# Schema.net
KiCad netlist of a schematic drawn in EAGLE
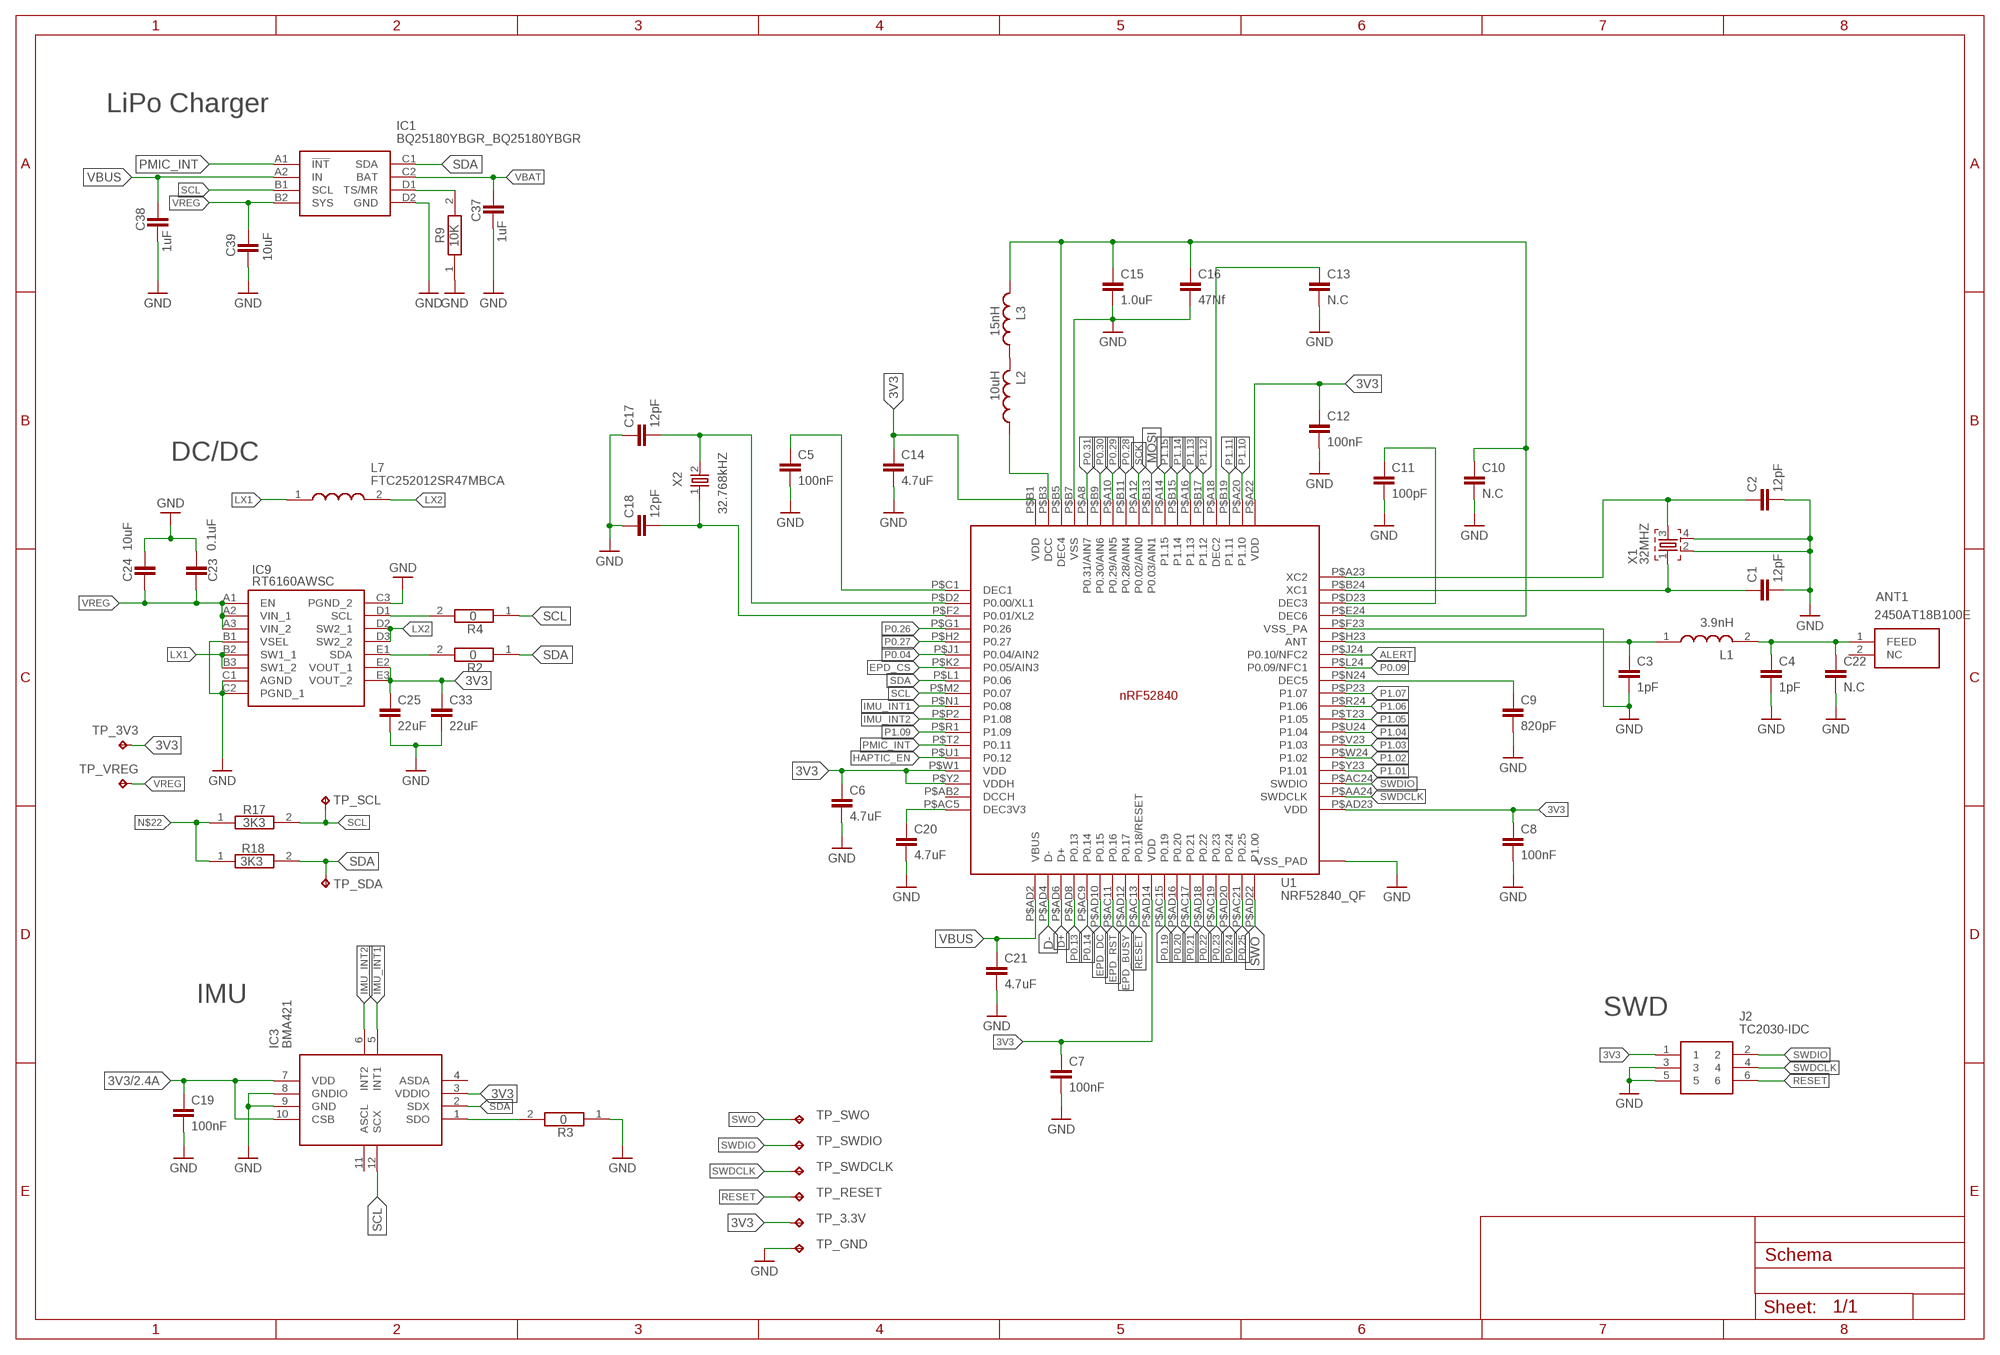
[diagram p0: schematic, sheet 1, part 1 of 2]
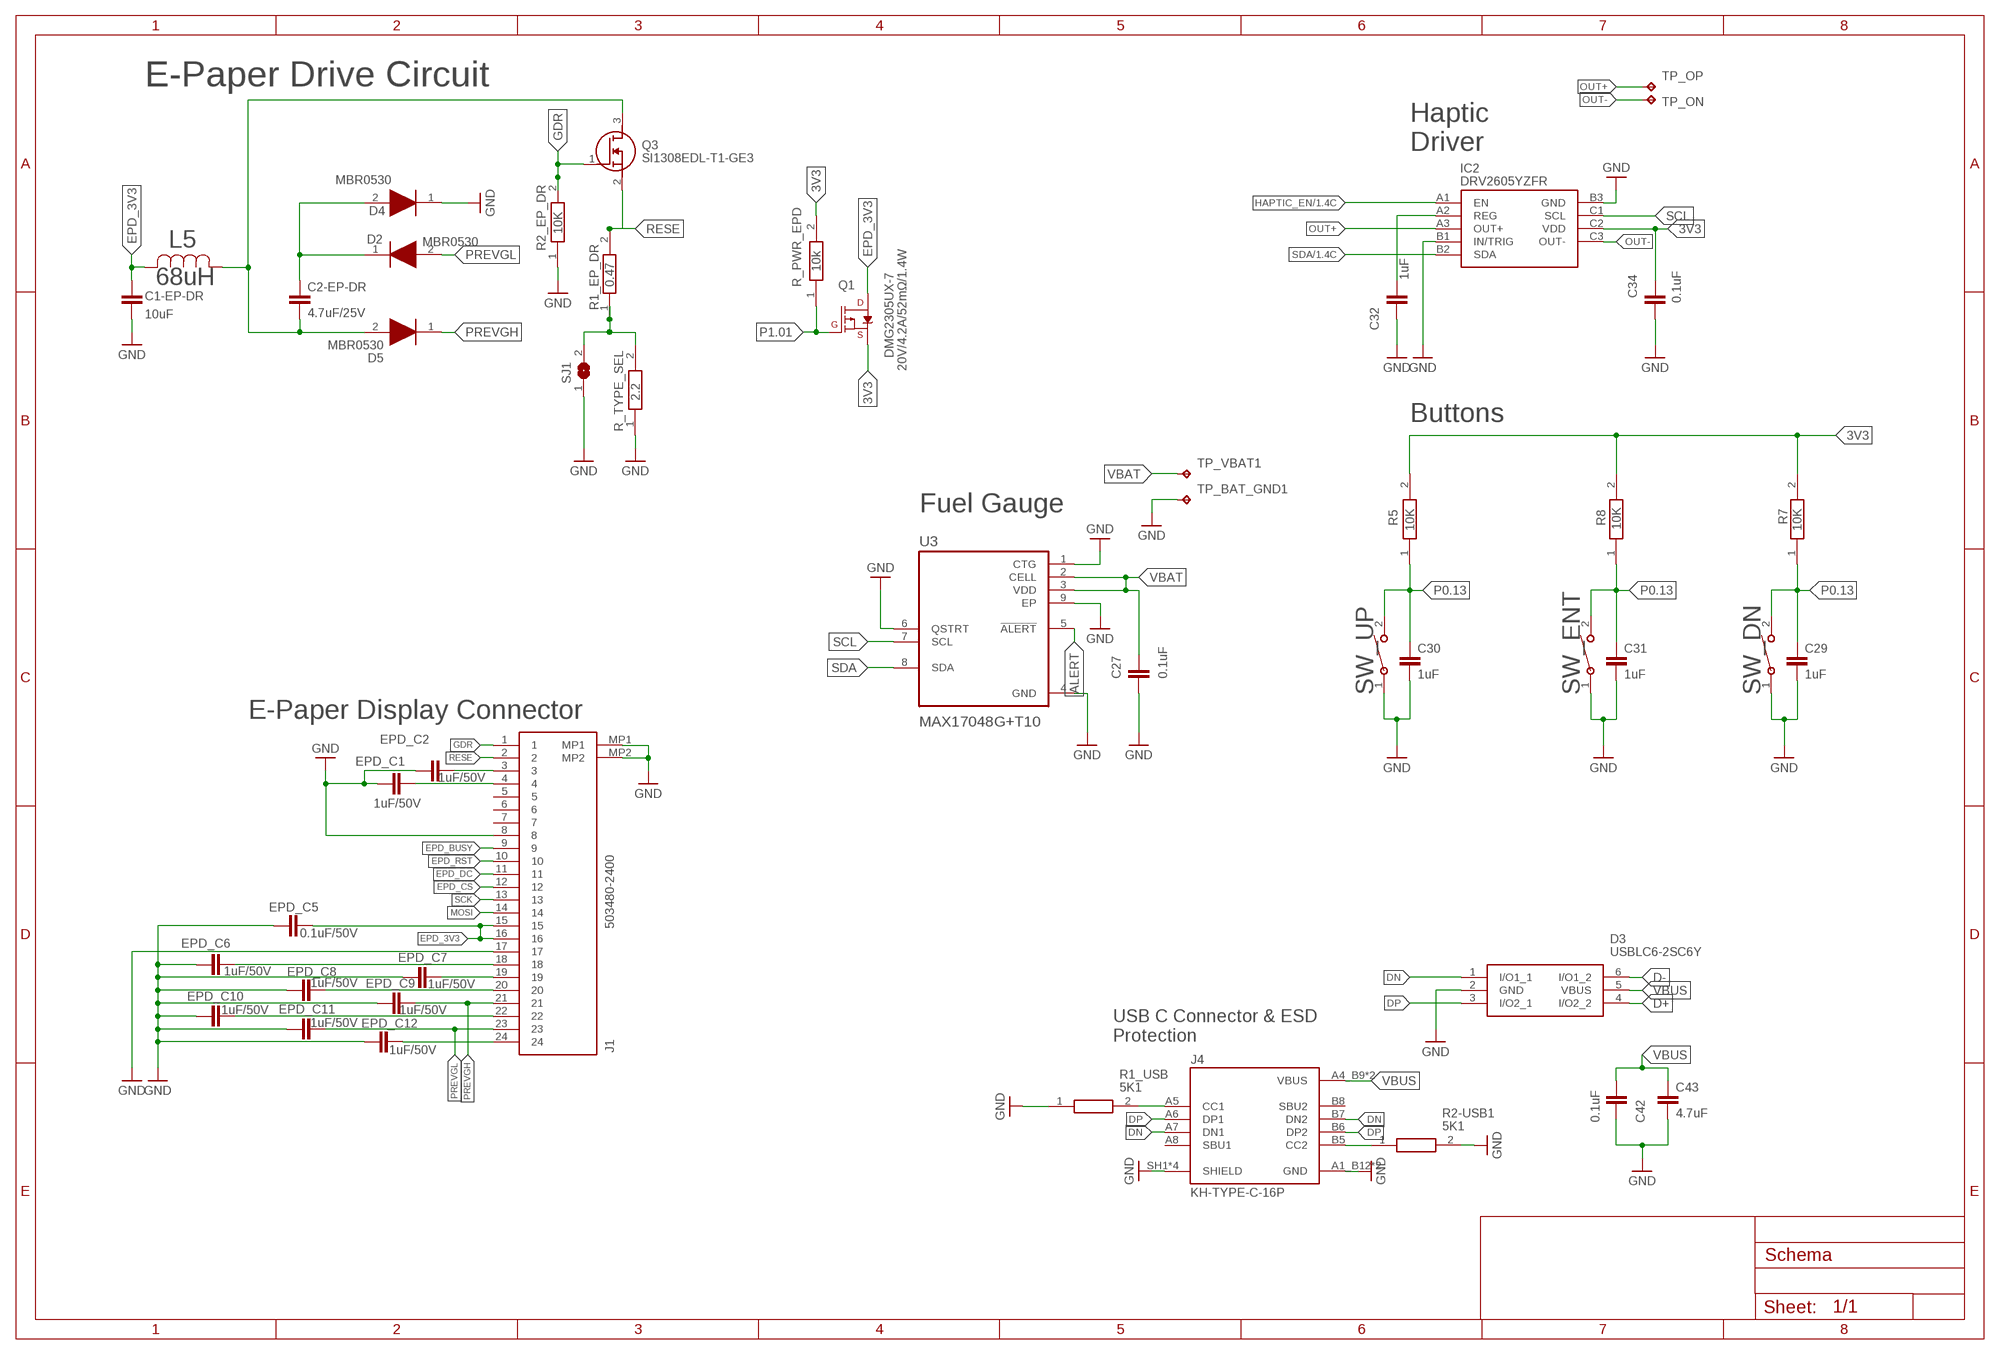
[diagram p1: schematic, sheet 1, part 2 of 2]

(export (version "E")
  (design (tool "Eeschema 10.0.6"))
  (components
    (comp (ref "ANT1")
      (value "2450AT18B100E")
      (footprint "eagle-import:2450AT18B100E_ANTC3216X140N")
      (fields (field (name "MOUSER_PART_NUMBER") "609-2450AT18B100E"))
      (libsource (lib "eagle-import") (part "2450AT18B100E_2450AT18B100E"))
    )
    (comp (ref "C1")
      (value "12pF")
      (footprint "eagle-import:NORDIC_NRF_3_RESC0201_L")
      (libsource (lib "eagle-import") (part "NORDIC_NRF_3_CAPACITOR_0201_L"))
    )
    (comp (ref "C1-EP-DR")
      (value "10uF")
      (footprint "eagle-import:NORDIC_NRF_3_RESC0402_L")
      (libsource (lib "eagle-import") (part "NORDIC_NRF_3_CAPACITOR_0402_L"))
    )
    (comp (ref "C2")
      (value "12pF")
      (footprint "eagle-import:NORDIC_NRF_3_RESC0201_L")
      (libsource (lib "eagle-import") (part "NORDIC_NRF_3_CAPACITOR_0201_L"))
    )
    (comp (ref "C2-EP-DR")
      (value "4.7uF/25V")
      (footprint "eagle-import:NORDIC_NRF_3_RESC0402_L")
      (libsource (lib "eagle-import") (part "NORDIC_NRF_3_CAPACITOR_0402_L"))
    )
    (comp (ref "C3")
      (value "1pF")
      (footprint "eagle-import:NORDIC_NRF_3_RESC0201_L")
      (libsource (lib "eagle-import") (part "NORDIC_NRF_3_CAPACITOR_0201_L"))
    )
    (comp (ref "C4")
      (value "1pF")
      (footprint "eagle-import:NORDIC_NRF_3_RESC0201_L")
      (libsource (lib "eagle-import") (part "NORDIC_NRF_3_CAPACITOR_0201_L"))
    )
    (comp (ref "C5")
      (value "100nF")
      (footprint "eagle-import:NORDIC_NRF_3_RESC0201_L")
      (libsource (lib "eagle-import") (part "NORDIC_NRF_3_CAPACITOR_0201_L"))
    )
    (comp (ref "C6")
      (value "4.7uF")
      (footprint "eagle-import:NORDIC_NRF_3_RESC0402_L")
      (libsource (lib "eagle-import") (part "NORDIC_NRF_3_CAPACITOR_0402_L"))
    )
    (comp (ref "C7")
      (value "100nF")
      (footprint "eagle-import:NORDIC_NRF_3_RESC0201_L")
      (libsource (lib "eagle-import") (part "NORDIC_NRF_3_CAPACITOR_0201_L"))
    )
    (comp (ref "C8")
      (value "100nF")
      (footprint "eagle-import:NORDIC_NRF_3_RESC0201_L")
      (libsource (lib "eagle-import") (part "NORDIC_NRF_3_CAPACITOR_0201_L"))
    )
    (comp (ref "C9")
      (value "820pF")
      (footprint "eagle-import:NORDIC_NRF_3_RESC0201_L")
      (libsource (lib "eagle-import") (part "NORDIC_NRF_3_CAPACITOR_0201_L"))
    )
    (comp (ref "C10")
      (value "N.C")
      (footprint "eagle-import:NORDIC_NRF_3_RESC0201_L")
      (libsource (lib "eagle-import") (part "NORDIC_NRF_3_CAPACITOR_0201_L"))
    )
    (comp (ref "C11")
      (value "100pF")
      (footprint "eagle-import:NORDIC_NRF_3_RESC0201_L")
      (libsource (lib "eagle-import") (part "NORDIC_NRF_3_CAPACITOR_0201_L"))
    )
    (comp (ref "C12")
      (value "100nF")
      (footprint "eagle-import:NORDIC_NRF_3_RESC0201_L")
      (libsource (lib "eagle-import") (part "NORDIC_NRF_3_CAPACITOR_0201_L"))
    )
    (comp (ref "C13")
      (value "N.C")
      (footprint "eagle-import:NORDIC_NRF_3_RESC0201_L")
      (libsource (lib "eagle-import") (part "NORDIC_NRF_3_CAPACITOR_0201_L"))
    )
    (comp (ref "C14")
      (value "4.7uF")
      (footprint "eagle-import:NORDIC_NRF_3_RESC0402_L")
      (libsource (lib "eagle-import") (part "NORDIC_NRF_3_CAPACITOR_0402_L"))
    )
    (comp (ref "C15")
      (value "1.0uF")
      (footprint "eagle-import:NORDIC_NRF_3_RESC0402_L")
      (libsource (lib "eagle-import") (part "NORDIC_NRF_3_CAPACITOR_0402_L"))
    )
    (comp (ref "C16")
      (value "47Nf")
      (footprint "eagle-import:NORDIC_NRF_3_RESC0201_L")
      (libsource (lib "eagle-import") (part "NORDIC_NRF_3_CAPACITOR_0201_L"))
    )
    (comp (ref "C17")
      (value "12pF")
      (footprint "eagle-import:NORDIC_NRF_3_RESC0201_L")
      (libsource (lib "eagle-import") (part "NORDIC_NRF_3_CAPACITOR_0201_L"))
    )
    (comp (ref "C18")
      (value "12pF")
      (footprint "eagle-import:NORDIC_NRF_3_RESC0201_L")
      (libsource (lib "eagle-import") (part "NORDIC_NRF_3_CAPACITOR_0201_L"))
    )
    (comp (ref "C19")
      (value "100nF")
      (footprint "eagle-import:NORDIC_NRF_3_RESC0201_L")
      (libsource (lib "eagle-import") (part "NORDIC_NRF_3_CAPACITOR_0201_L"))
    )
    (comp (ref "C20")
      (value "4.7uF")
      (footprint "eagle-import:NORDIC_NRF_3_RESC0402_L")
      (libsource (lib "eagle-import") (part "NORDIC_NRF_3_CAPACITOR_0402_L"))
    )
    (comp (ref "C21")
      (value "4.7uF")
      (footprint "eagle-import:NORDIC_NRF_3_RESC0402_L")
      (libsource (lib "eagle-import") (part "NORDIC_NRF_3_CAPACITOR_0402_L"))
    )
    (comp (ref "C22")
      (value "N.C")
      (footprint "eagle-import:NORDIC_NRF_3_RESC0201_L")
      (libsource (lib "eagle-import") (part "NORDIC_NRF_3_CAPACITOR_0201_L"))
    )
    (comp (ref "C23")
      (value "0.1uF")
      (footprint "eagle-import:NORDIC_NRF_3_RESC0402_L")
      (libsource (lib "eagle-import") (part "NORDIC_NRF_3_CAPACITOR_0402_L"))
    )
    (comp (ref "C24")
      (value "10uF")
      (footprint "eagle-import:NORDIC_NRF_3_RESC0201_L")
      (libsource (lib "eagle-import") (part "NORDIC_NRF_3_CAPACITOR_0201_L"))
    )
    (comp (ref "C25")
      (value "22uF")
      (footprint "eagle-import:NORDIC_NRF_3_RESC0402_L")
      (libsource (lib "eagle-import") (part "NORDIC_NRF_3_CAPACITOR_0402_L"))
    )
    (comp (ref "C27")
      (value "0.1uF")
      (footprint "eagle-import:NORDIC_NRF_3_RESC0201_L")
      (libsource (lib "eagle-import") (part "NORDIC_NRF_3_CAPACITOR_0201_L"))
    )
    (comp (ref "C29")
      (value "1uF")
      (footprint "eagle-import:NORDIC_NRF_3_RESC0402_L")
      (libsource (lib "eagle-import") (part "NORDIC_NRF_3_CAPACITOR_0402_L"))
    )
    (comp (ref "C30")
      (value "1uF")
      (footprint "eagle-import:NORDIC_NRF_3_RESC0402_L")
      (libsource (lib "eagle-import") (part "NORDIC_NRF_3_CAPACITOR_0402_L"))
    )
    (comp (ref "C31")
      (value "1uF")
      (footprint "eagle-import:NORDIC_NRF_3_RESC0402_L")
      (libsource (lib "eagle-import") (part "NORDIC_NRF_3_CAPACITOR_0402_L"))
    )
    (comp (ref "C32")
      (value "1uF")
      (footprint "eagle-import:NORDIC_NRF_3_RESC0402_L")
      (libsource (lib "eagle-import") (part "NORDIC_NRF_3_CAPACITOR_0402_L"))
    )
    (comp (ref "C33")
      (value "22uF")
      (footprint "eagle-import:NORDIC_NRF_3_RESC0402_L")
      (libsource (lib "eagle-import") (part "NORDIC_NRF_3_CAPACITOR_0402_L"))
    )
    (comp (ref "C34")
      (value "0.1uF")
      (footprint "eagle-import:NORDIC_NRF_3_RESC0201_L")
      (libsource (lib "eagle-import") (part "NORDIC_NRF_3_CAPACITOR_0201_L"))
    )
    (comp (ref "C37")
      (value "1uF")
      (footprint "eagle-import:PERFECT_0402_0402")
      (libsource (lib "eagle-import") (part "PERFECT_0402_CAP_0402"))
    )
    (comp (ref "C38")
      (value "1uF")
      (footprint "eagle-import:PERFECT_0402_0402")
      (libsource (lib "eagle-import") (part "PERFECT_0402_CAP_0402"))
    )
    (comp (ref "C39")
      (value "10uF")
      (footprint "eagle-import:PERFECT_0402_0402")
      (libsource (lib "eagle-import") (part "PERFECT_0402_CAP_0402"))
    )
    (comp (ref "C42")
      (value "0.1uF")
      (footprint "eagle-import:NORDIC_NRF_3_RESC0201_L")
      (libsource (lib "eagle-import") (part "NORDIC_NRF_3_CAPACITOR_0201_L"))
    )
    (comp (ref "C43")
      (value "4.7uF")
      (footprint "eagle-import:NORDIC_NRF_3_RESC0402_L")
      (libsource (lib "eagle-import") (part "NORDIC_NRF_3_CAPACITOR_0402_L"))
    )
    (comp (ref "D2")
      (value "MBR0530")
      (footprint "eagle-import:ESP32_C6_LIBRARY_5_SOD3716X135N")
      (fields (field (name "MF") "ON Semiconductor"))
      (libsource (lib "eagle-import") (part "ESP32_C6_LIBRARY_5_MBR0530"))
    )
    (comp (ref "D3")
      (value "USBLC6-2SC6Y")
      (footprint "eagle-import:ESP32_C6_LIBRARY_3_SOT95P280X145-6N")
      (fields (field (name "MF") "STMicroelectronics"))
      (libsource (lib "eagle-import") (part "ESP32_C6_LIBRARY_3_USBLC6-2SC6Y"))
    )
    (comp (ref "D4")
      (value "MBR0530")
      (footprint "eagle-import:ESP32_C6_LIBRARY_5_SOD3716X135N")
      (fields (field (name "MF") "ON Semiconductor"))
      (libsource (lib "eagle-import") (part "ESP32_C6_LIBRARY_5_MBR0530"))
    )
    (comp (ref "D5")
      (value "MBR0530")
      (footprint "eagle-import:ESP32_C6_LIBRARY_5_SOD3716X135N")
      (fields (field (name "MF") "ON Semiconductor"))
      (libsource (lib "eagle-import") (part "ESP32_C6_LIBRARY_5_MBR0530"))
    )
    (comp (ref "EPD_C1")
      (value "1uF/50V")
      (footprint "eagle-import:NORDIC_NRF_3_RESC0402_L")
      (libsource (lib "eagle-import") (part "NORDIC_NRF_3_CAPACITOR_0402_L"))
    )
    (comp (ref "EPD_C2")
      (value "1uF/50V")
      (footprint "eagle-import:NORDIC_NRF_3_RESC0402_L")
      (libsource (lib "eagle-import") (part "NORDIC_NRF_3_CAPACITOR_0402_L"))
    )
    (comp (ref "EPD_C5")
      (value "0.1uF/50V")
      (footprint "eagle-import:NORDIC_NRF_3_RESC0201_L")
      (libsource (lib "eagle-import") (part "NORDIC_NRF_3_CAPACITOR_0201_L"))
    )
    (comp (ref "EPD_C6")
      (value "1uF/50V")
      (footprint "eagle-import:NORDIC_NRF_3_RESC0402_L")
      (libsource (lib "eagle-import") (part "NORDIC_NRF_3_CAPACITOR_0402_L"))
    )
    (comp (ref "EPD_C7")
      (value "1uF/50V")
      (footprint "eagle-import:NORDIC_NRF_3_RESC0402_L")
      (libsource (lib "eagle-import") (part "NORDIC_NRF_3_CAPACITOR_0402_L"))
    )
    (comp (ref "EPD_C8")
      (value "1uF/50V")
      (footprint "eagle-import:NORDIC_NRF_3_RESC0402_L")
      (libsource (lib "eagle-import") (part "NORDIC_NRF_3_CAPACITOR_0402_L"))
    )
    (comp (ref "EPD_C9")
      (value "1uF/50V")
      (footprint "eagle-import:NORDIC_NRF_3_RESC0402_L")
      (libsource (lib "eagle-import") (part "NORDIC_NRF_3_CAPACITOR_0402_L"))
    )
    (comp (ref "EPD_C10")
      (value "1uF/50V")
      (footprint "eagle-import:NORDIC_NRF_3_RESC0402_L")
      (libsource (lib "eagle-import") (part "NORDIC_NRF_3_CAPACITOR_0402_L"))
    )
    (comp (ref "EPD_C11")
      (value "1uF/50V")
      (footprint "eagle-import:NORDIC_NRF_3_RESC0402_L")
      (libsource (lib "eagle-import") (part "NORDIC_NRF_3_CAPACITOR_0402_L"))
    )
    (comp (ref "EPD_C12")
      (value "1uF/50V")
      (footprint "eagle-import:NORDIC_NRF_3_RESC0402_L")
      (libsource (lib "eagle-import") (part "NORDIC_NRF_3_CAPACITOR_0402_L"))
    )
    (comp (ref "IC1")
      (value "BQ25180YBGR_BQ25180YBGR")
      (footprint "eagle-import:BQ25180YBGR_BGA8C40P2X4_100X155X50")
      (fields
        (field (name "ARROW_PART_NUMBER") "BQ25180YBGR")
        (field (name "MOUSER_PART_NUMBER") "595-BQ25180YBGR")
      )
      (libsource (lib "eagle-import") (part "BQ25180YBGR_BQ25180YBGR"))
    )
    (comp (ref "IC2")
      (value "DRV2605YZFR")
      (footprint "eagle-import:DRV2605YZFR_BGA9C50P3X3_144X144X62")
      (libsource (lib "eagle-import") (part "DRV2605YZFR_DRV2605YZFR"))
    )
    (comp (ref "IC3")
      (value "BMA421")
      (footprint "eagle-import:BMA423_BMA423")
      (fields (field (name "ARROW_PART_NUMBER") "BMA423") (field (name "MOUSER_PART_NUMBER") "262-BMA423"))
      (libsource (lib "eagle-import") (part "BMA423_BMA423"))
    )
    (comp (ref "IC9")
      (value "RT6160AWSC")
      (footprint "eagle-import:RT6160AWSC_BGA15C40P3X5_140X230X60")
      (fields (field (name "MOUSER_PART_NUMBER") "835-RT6160AWSC"))
      (libsource (lib "eagle-import") (part "RT6160AWSC_RT6160AWSC"))
    )
    (comp (ref "J1")
      (value "503480-2400")
      (footprint "eagle-import:503480-2400_5034802400")
      (fields (field (name "MOUSER_PART_NUMBER") "538-503480-2400"))
      (libsource (lib "eagle-import") (part "503480-2400_503480-2400"))
    )
    (comp (ref "J2")
      (value "TC2030-IDC")
      (footprint "eagle-import:TC2030-IDC_TC2030IDC")
      (libsource (lib "eagle-import") (part "TC2030-IDC_TC2030-IDC"))
    )
    (comp (ref "J4")
      (value "KH-TYPE-C-16P")
      (footprint "eagle-import:KH-TYPE-C-16P_KINGHELM_KH-TYPE-C-16P")
      (fields (field (name "MF") "kinghelm"))
      (libsource (lib "eagle-import") (part "KH-TYPE-C-16P_KH-TYPE-C-16P"))
    )
    (comp (ref "L1")
      (value "3.9nH")
      (footprint "eagle-import:MLP2016SR47MT0S1_INDC2016X100N")
      (fields (field (name "MANUFACTURER_PART_NUMBER") "FTC252012SR47MBCA"))
      (libsource (lib "eagle-import") (part "MLP2016SR47MT0S1_FTC252012SR47MBCA"))
    )
    (comp (ref "L2")
      (value "10uH")
      (footprint "eagle-import:NORDIC_NRF_2_RESC0402_L")
      (libsource (lib "eagle-import") (part "NORDIC_NRF_2_INDUCTOR_0402_L"))
    )
    (comp (ref "L3")
      (value "15nH")
      (footprint "eagle-import:NORDIC_NRF_2_RESC0402_L")
      (libsource (lib "eagle-import") (part "NORDIC_NRF_2_INDUCTOR_0402_L"))
    )
    (comp (ref "L5")
      (value "68uH")
      (footprint "eagle-import:ESP32_C6_LIBRARY_2_IND_4828-WE-TPC_WRE")
      (fields
        (field (name "MANUFACTURER_PART_NUMBER") "744043680")
        (field (name "COPYRIGHT") "Copyright (C) 2024 Ultra Librarian. All rights reserved.")
      )
      (libsource (lib "eagle-import") (part "ESP32_C6_LIBRARY_2_744043680IND_4828-WE-TPC_WRE"))
    )
    (comp (ref "L7")
      (value "FTC252012SR47MBCA")
      (footprint "eagle-import:MLP2016SR47MT0S1_INDC2016X100N")
      (libsource (lib "eagle-import") (part "MLP2016SR47MT0S1_FTC252012SR47MBCA"))
    )
    (comp (ref "Q1")
      (value "20V/4.2A/52mΩ/1.4W")
      (footprint "eagle-import:ESP32_C6_LIBRARY_4_ESP32_C6_LIBRARY_4_ESP32_C6_LIBRARY_4_ESP32_C6_LIBRARY_4_ESP32_WROVER_SPARKFUN-DISCRETESEMI_SOT23-3")
      (libsource (lib "eagle-import") (part "ESP32_C6_LIBRARY_4_ESP32_WROVER_SPARKFUN-DISCRETESEMI_MOSFET_PCH-DMG2305UX-7"))
    )
    (comp (ref "Q3")
      (value "SI1308EDL-T1-GE3")
      (footprint "eagle-import:ESP32_C6_LIBRARY_6_SOT65P210X110-3N")
      (fields (field (name "MF") "Vishay Siliconix"))
      (libsource (lib "eagle-import") (part "ESP32_C6_LIBRARY_6_SI1308EDL-T1-GE3"))
    )
    (comp (ref "R1_EP_DR")
      (value "0.47")
      (footprint "eagle-import:CPF0201D7K68C1_0201")
      (libsource (lib "eagle-import") (part "CPF0201D7K68C1_CPF0201D7K68C1"))
    )
    (comp (ref "R1_USB")
      (value "5K1")
      (footprint "eagle-import:CPF0201D7K68C1_0201")
      (libsource (lib "eagle-import") (part "CPF0201D7K68C1_CPF0201D7K68C1"))
    )
    (comp (ref "R2")
      (value "0")
      (footprint "eagle-import:CPF0201D7K68C1_0201")
      (libsource (lib "eagle-import") (part "CPF0201D7K68C1_CPF0201D7K68C1"))
    )
    (comp (ref "R2-USB1")
      (value "5K1")
      (footprint "eagle-import:CPF0201D7K68C1_0201")
      (libsource (lib "eagle-import") (part "CPF0201D7K68C1_CPF0201D7K68C1"))
    )
    (comp (ref "R2_EP_DR")
      (value "10K")
      (footprint "eagle-import:CPF0201D7K68C1_0201")
      (libsource (lib "eagle-import") (part "CPF0201D7K68C1_CPF0201D7K68C1"))
    )
    (comp (ref "R3")
      (value "0")
      (footprint "eagle-import:CPF0201D7K68C1_0201")
      (libsource (lib "eagle-import") (part "CPF0201D7K68C1_CPF0201D7K68C1"))
    )
    (comp (ref "R4")
      (value "0")
      (footprint "eagle-import:CPF0201D7K68C1_0201")
      (libsource (lib "eagle-import") (part "CPF0201D7K68C1_CPF0201D7K68C1"))
    )
    (comp (ref "R5")
      (value "10K")
      (footprint "eagle-import:CPF0201D7K68C1_0201")
      (libsource (lib "eagle-import") (part "CPF0201D7K68C1_CPF0201D7K68C1"))
    )
    (comp (ref "R7")
      (value "10K")
      (footprint "eagle-import:CPF0201D7K68C1_0201")
      (libsource (lib "eagle-import") (part "CPF0201D7K68C1_CPF0201D7K68C1"))
    )
    (comp (ref "R8")
      (value "10K")
      (footprint "eagle-import:CPF0201D7K68C1_0201")
      (libsource (lib "eagle-import") (part "CPF0201D7K68C1_CPF0201D7K68C1"))
    )
    (comp (ref "R9")
      (value "10K")
      (footprint "eagle-import:CPF0201D7K68C1_0201")
      (libsource (lib "eagle-import") (part "CPF0201D7K68C1_CPF0201D7K68C1"))
    )
    (comp (ref "R17")
      (value "3K3")
      (footprint "eagle-import:CPF0201D7K68C1_0201")
      (libsource (lib "eagle-import") (part "CPF0201D7K68C1_CPF0201D7K68C1"))
    )
    (comp (ref "R18")
      (value "3K3")
      (footprint "eagle-import:CPF0201D7K68C1_0201")
      (libsource (lib "eagle-import") (part "CPF0201D7K68C1_CPF0201D7K68C1"))
    )
    (comp (ref "R_PWR_EPD")
      (value "10k")
      (footprint "eagle-import:CPF0201D7K68C1_0201")
      (libsource (lib "eagle-import") (part "CPF0201D7K68C1_CPF0201D7K68C1"))
    )
    (comp (ref "R_TYPE_SEL")
      (value "2.2")
      (footprint "eagle-import:CPF0201D7K68C1_0201")
      (libsource (lib "eagle-import") (part "CPF0201D7K68C1_CPF0201D7K68C1"))
    )
    (comp (ref "SJ1")
      (value "ESP32_C6_LIBRARY_7_JUMPER_SJ")
      (footprint "eagle-import:ESP32_C6_LIBRARY_7_JUMPER_SJ")
      (libsource (lib "eagle-import") (part "ESP32_C6_LIBRARY_7_JUMPER_SJ"))
    )
    (comp (ref "SW_DN")
      (value "2025-10-22_07-23-44_LIBRARY_EVP-AKE31ASW_EVP-AKE31A_PAN")
      (footprint "eagle-import:2025-10-22_07-23-44_LIBRARY_SW_EVP-AKE31A_PAN")
      (fields
        (field (name "MANUFACTURER_PART_NUMBER") "EVP-AKE31A")
        (field (name "COPYRIGHT") "Copyright (C) 2025 Ultra Librarian. All rights reserved.")
      )
      (libsource (lib "eagle-import") (part "2025-10-22_07-23-44_LIBRARY_EVP-AKE31ASW_EVP-AKE31A_PAN"))
    )
    (comp (ref "SW_ENT")
      (value "2025-10-22_07-23-44_LIBRARY_EVP-AKE31ASW_EVP-AKE31A_PAN")
      (footprint "eagle-import:2025-10-22_07-23-44_LIBRARY_SW_EVP-AKE31A_PAN")
      (fields
        (field (name "MANUFACTURER_PART_NUMBER") "EVP-AKE31A")
        (field (name "COPYRIGHT") "Copyright (C) 2025 Ultra Librarian. All rights reserved.")
      )
      (libsource (lib "eagle-import") (part "2025-10-22_07-23-44_LIBRARY_EVP-AKE31ASW_EVP-AKE31A_PAN"))
    )
    (comp (ref "SW_UP")
      (value "2025-10-22_07-23-44_LIBRARY_EVP-AKE31ASW_EVP-AKE31A_PAN")
      (footprint "eagle-import:2025-10-22_07-23-44_LIBRARY_SW_EVP-AKE31A_PAN")
      (fields
        (field (name "MANUFACTURER_PART_NUMBER") "EVP-AKE31A")
        (field (name "COPYRIGHT") "Copyright (C) 2025 Ultra Librarian. All rights reserved.")
      )
      (libsource (lib "eagle-import") (part "2025-10-22_07-23-44_LIBRARY_EVP-AKE31ASW_EVP-AKE31A_PAN"))
    )
    (comp (ref "TP_3.3V")
      (value "HECTOR_WATCH_1_TPTP20R")
      (footprint "eagle-import:HECTOR_WATCH_1_TP20R")
      (libsource (lib "eagle-import") (part "HECTOR_WATCH_1_TPTP20R"))
    )
    (comp (ref "TP_3V3")
      (value "HECTOR_WATCH_1_TPTP20R")
      (footprint "eagle-import:HECTOR_WATCH_1_TP20R")
      (libsource (lib "eagle-import") (part "HECTOR_WATCH_1_TPTP20R"))
    )
    (comp (ref "TP_BAT_GND1")
      (value "HECTOR_WATCH_1_TPTP20R")
      (footprint "eagle-import:HECTOR_WATCH_1_TP20R")
      (libsource (lib "eagle-import") (part "HECTOR_WATCH_1_TPTP20R"))
    )
    (comp (ref "TP_GND")
      (value "HECTOR_WATCH_1_TPTP20R")
      (footprint "eagle-import:HECTOR_WATCH_1_TP20R")
      (libsource (lib "eagle-import") (part "HECTOR_WATCH_1_TPTP20R"))
    )
    (comp (ref "TP_ON")
      (value "HECTOR_WATCH_1_TPTP20R")
      (footprint "eagle-import:HECTOR_WATCH_1_TP20R")
      (libsource (lib "eagle-import") (part "HECTOR_WATCH_1_TPTP20R"))
    )
    (comp (ref "TP_OP")
      (value "HECTOR_WATCH_1_TPTP20R")
      (footprint "eagle-import:HECTOR_WATCH_1_TP20R")
      (libsource (lib "eagle-import") (part "HECTOR_WATCH_1_TPTP20R"))
    )
    (comp (ref "TP_RESET")
      (value "HECTOR_WATCH_1_TPTP20R")
      (footprint "eagle-import:HECTOR_WATCH_1_TP20R")
      (libsource (lib "eagle-import") (part "HECTOR_WATCH_1_TPTP20R"))
    )
    (comp (ref "TP_SCL")
      (value "HECTOR_WATCH_1_TPTP20R")
      (footprint "eagle-import:HECTOR_WATCH_1_TP20R")
      (libsource (lib "eagle-import") (part "HECTOR_WATCH_1_TPTP20R"))
    )
    (comp (ref "TP_SDA")
      (value "HECTOR_WATCH_1_TPTP20R")
      (footprint "eagle-import:HECTOR_WATCH_1_TP20R")
      (libsource (lib "eagle-import") (part "HECTOR_WATCH_1_TPTP20R"))
    )
    (comp (ref "TP_SWDCLK")
      (value "HECTOR_WATCH_1_TPTP20R")
      (footprint "eagle-import:HECTOR_WATCH_1_TP20R")
      (libsource (lib "eagle-import") (part "HECTOR_WATCH_1_TPTP20R"))
    )
    (comp (ref "TP_SWDIO")
      (value "HECTOR_WATCH_1_TPTP20R")
      (footprint "eagle-import:HECTOR_WATCH_1_TP20R")
      (libsource (lib "eagle-import") (part "HECTOR_WATCH_1_TPTP20R"))
    )
    (comp (ref "TP_SWO")
      (value "HECTOR_WATCH_1_TPTP20R")
      (footprint "eagle-import:HECTOR_WATCH_1_TP20R")
      (libsource (lib "eagle-import") (part "HECTOR_WATCH_1_TPTP20R"))
    )
    (comp (ref "TP_VBAT1")
      (value "HECTOR_WATCH_1_TPTP20R")
      (footprint "eagle-import:HECTOR_WATCH_1_TP20R")
      (libsource (lib "eagle-import") (part "HECTOR_WATCH_1_TPTP20R"))
    )
    (comp (ref "TP_VREG")
      (value "HECTOR_WATCH_1_TPTP20R")
      (footprint "eagle-import:HECTOR_WATCH_1_TP20R")
      (libsource (lib "eagle-import") (part "HECTOR_WATCH_1_TPTP20R"))
    )
    (comp (ref "U1")
      (value "NRF52840_QF")
      (footprint "eagle-import:NORDIC_NRF_4_AQFN50P700X700X85_HS-74N")
      (libsource (lib "eagle-import") (part "NORDIC_NRF_4_NRF52840_QF"))
    )
    (comp (ref "U3")
      (value "MAX17048G+T10")
      (footprint "eagle-import:ESP32_C6_LIBRARY_SON50P200X200X80-9N")
      (fields (field (name "MF") "Analog Devices"))
      (libsource (lib "eagle-import") (part "ESP32_C6_LIBRARY_MAX17048G+T10"))
    )
    (comp (ref "X1")
      (value "32MHZ")
      (footprint "eagle-import:NORDIC_NRF_BT-XTAL_2016_N")
      (libsource (lib "eagle-import") (part "NORDIC_NRF_XTAL_32MHZ"))
    )
    (comp (ref "X2")
      (value "32.768kHZ")
      (footprint "eagle-import:NORDIC_NRF_1_XTAL_3215_N")
      (libsource (lib "eagle-import") (part "NORDIC_NRF_1_XTAL_32KHZ"))
    )
  )
  (nets
    (net (code "1") (name "3V3") (class "Default")
      (node (ref "C12") (pin "1") (pinfunction "1_1") (pintype "passive"))
      (node (ref "C14") (pin "1") (pinfunction "1_1") (pintype "passive"))
      (node (ref "C25") (pin "1") (pinfunction "1_1") (pintype "passive"))
      (node (ref "C33") (pin "1") (pinfunction "1_1") (pintype "passive"))
      (node (ref "C34") (pin "1") (pinfunction "1_1") (pintype "passive"))
      (node (ref "C6") (pin "1") (pinfunction "1_1") (pintype "passive"))
      (node (ref "C7") (pin "1") (pinfunction "1_1") (pintype "passive"))
      (node (ref "C8") (pin "1") (pinfunction "1_1") (pintype "passive"))
      (node (ref "IC2") (pin "C2") (pinfunction "VDD_C2") (pintype "bidirectional"))
      (node (ref "IC3") (pin "3") (pinfunction "VDDIO_3") (pintype "bidirectional"))
      (node (ref "IC9") (pin "E2") (pinfunction "VOUT_1_E2") (pintype "bidirectional"))
      (node (ref "IC9") (pin "E3") (pinfunction "VOUT_2_E3") (pintype "bidirectional"))
      (node (ref "J2") (pin "1") (pinfunction "1_1") (pintype "bidirectional"))
      (node (ref "Q1") (pin "2") (pinfunction "S_2") (pintype "bidirectional"))
      (node (ref "R5") (pin "2") (pinfunction "2_2") (pintype "bidirectional"))
      (node (ref "R7") (pin "2") (pinfunction "2_2") (pintype "bidirectional"))
      (node (ref "R8") (pin "2") (pinfunction "2_2") (pintype "bidirectional"))
      (node (ref "R_PWR_EPD") (pin "2") (pinfunction "2_2") (pintype "bidirectional"))
      (node (ref "TP_3.3V") (pin "TP") (pinfunction "TP_TP") (pintype "input"))
      (node (ref "TP_3V3") (pin "TP") (pinfunction "TP_TP") (pintype "input"))
      (node (ref "U1") (pin "P$A22") (pinfunction "VDD_P$A22") (pintype "power_in"))
      (node (ref "U1") (pin "P$AD14") (pinfunction "VDD_P$AD14") (pintype "power_in"))
      (node (ref "U1") (pin "P$AD23") (pinfunction "VDD_P$AD23") (pintype "power_in"))
      (node (ref "U1") (pin "P$B1") (pinfunction "VDD_P$B1") (pintype "power_in"))
      (node (ref "U1") (pin "P$W1") (pinfunction "VDD_P$W1") (pintype "power_in"))
      (node (ref "U1") (pin "P$Y2") (pinfunction "VDDH_P$Y2") (pintype "power_in"))
    )
    (net (code "2") (name "3V3{slash}2.4A") (class "Default")
      (node (ref "C19") (pin "1") (pinfunction "1_1") (pintype "passive"))
      (node (ref "IC3") (pin "10") (pinfunction "CSB_10") (pintype "bidirectional"))
      (node (ref "IC3") (pin "7") (pinfunction "VDD_7") (pintype "bidirectional"))
    )
    (net (code "3") (name "ALERT") (class "Default")
      (node (ref "U1") (pin "P$J24") (pinfunction "P0.10/NFC2_P$J24") (pintype "bidirectional"))
      (node (ref "U3") (pin "5") (pinfunction "~{ALERT}_5") (pintype "output"))
    )
    (net (code "4") (name "D+") (class "Default")
      (node (ref "D3") (pin "4") (pinfunction "I/O2_2_4") (pintype "bidirectional"))
      (node (ref "U1") (pin "P$AD6") (pinfunction "D+_P$AD6") (pintype "bidirectional"))
    )
    (net (code "5") (name "D-") (class "Default")
      (node (ref "D3") (pin "6") (pinfunction "I/O1_2_6") (pintype "bidirectional"))
      (node (ref "U1") (pin "P$AD4") (pinfunction "D-_P$AD4") (pintype "bidirectional"))
    )
    (net (code "6") (name "DN") (class "Default")
      (node (ref "D3") (pin "1") (pinfunction "I/O1_1_1") (pintype "bidirectional"))
      (node (ref "J4") (pin "A7") (pinfunction "DN1_A7") (pintype "bidirectional"))
      (node (ref "J4") (pin "B7") (pinfunction "DN2_B7") (pintype "bidirectional"))
    )
    (net (code "7") (name "DP") (class "Default")
      (node (ref "D3") (pin "3") (pinfunction "I/O2_1_3") (pintype "bidirectional"))
      (node (ref "J4") (pin "A6") (pinfunction "DP1_A6") (pintype "bidirectional"))
      (node (ref "J4") (pin "B6") (pinfunction "DP2_B6") (pintype "bidirectional"))
    )
    (net (code "8") (name "EPD_3V3") (class "Default")
      (node (ref "C1-EP-DR") (pin "1") (pinfunction "1_1") (pintype "passive"))
      (node (ref "EPD_C5") (pin "2") (pinfunction "2_2") (pintype "passive"))
      (node (ref "J1") (pin "15") (pinfunction "15_15") (pintype "bidirectional"))
      (node (ref "J1") (pin "16") (pinfunction "16_16") (pintype "bidirectional"))
      (node (ref "L5") (pin "2") (pinfunction "2_2") (pintype "passive"))
      (node (ref "Q1") (pin "3") (pinfunction "D_3") (pintype "bidirectional"))
    )
    (net (code "9") (name "EPD_BUSY") (class "Default")
      (node (ref "J1") (pin "9") (pinfunction "9_9") (pintype "bidirectional"))
      (node (ref "U1") (pin "P$AD12") (pinfunction "P0.17_P$AD12") (pintype "bidirectional"))
    )
    (net (code "10") (name "EPD_CS") (class "Default")
      (node (ref "J1") (pin "12") (pinfunction "12_12") (pintype "bidirectional"))
      (node (ref "U1") (pin "P$K2") (pinfunction "P0.05/AIN3_P$K2") (pintype "bidirectional"))
    )
    (net (code "11") (name "EPD_DC") (class "Default")
      (node (ref "J1") (pin "11") (pinfunction "11_11") (pintype "bidirectional"))
      (node (ref "U1") (pin "P$AD10") (pinfunction "P0.15_P$AD10") (pintype "bidirectional"))
    )
    (net (code "12") (name "EPD_RST") (class "Default")
      (node (ref "J1") (pin "10") (pinfunction "10_10") (pintype "bidirectional"))
      (node (ref "U1") (pin "P$AC11") (pinfunction "P0.16_P$AC11") (pintype "bidirectional"))
    )
    (net (code "13") (name "GDR") (class "Default")
      (node (ref "J1") (pin "1") (pinfunction "1_1") (pintype "bidirectional"))
      (node (ref "Q3") (pin "1") (pinfunction "G_1") (pintype "bidirectional"))
      (node (ref "R2_EP_DR") (pin "2") (pinfunction "2_2") (pintype "bidirectional"))
    )
    (net (code "14") (name "GND") (class "Default")
      (node (ref "C1") (pin "2") (pinfunction "2_2") (pintype "passive"))
      (node (ref "C1-EP-DR") (pin "2") (pinfunction "2_2") (pintype "passive"))
      (node (ref "C10") (pin "2") (pinfunction "2_2") (pintype "passive"))
      (node (ref "C11") (pin "2") (pinfunction "2_2") (pintype "passive"))
      (node (ref "C12") (pin "2") (pinfunction "2_2") (pintype "passive"))
      (node (ref "C13") (pin "2") (pinfunction "2_2") (pintype "passive"))
      (node (ref "C14") (pin "2") (pinfunction "2_2") (pintype "passive"))
      (node (ref "C15") (pin "2") (pinfunction "2_2") (pintype "passive"))
      (node (ref "C16") (pin "2") (pinfunction "2_2") (pintype "passive"))
      (node (ref "C17") (pin "1") (pinfunction "1_1") (pintype "passive"))
      (node (ref "C18") (pin "1") (pinfunction "1_1") (pintype "passive"))
      (node (ref "C19") (pin "2") (pinfunction "2_2") (pintype "passive"))
      (node (ref "C2") (pin "2") (pinfunction "2_2") (pintype "passive"))
      (node (ref "C20") (pin "2") (pinfunction "2_2") (pintype "passive"))
      (node (ref "C21") (pin "2") (pinfunction "2_2") (pintype "passive"))
      (node (ref "C22") (pin "2") (pinfunction "2_2") (pintype "passive"))
      (node (ref "C23") (pin "1") (pinfunction "1_1") (pintype "passive"))
      (node (ref "C24") (pin "1") (pinfunction "1_1") (pintype "passive"))
      (node (ref "C25") (pin "2") (pinfunction "2_2") (pintype "passive"))
      (node (ref "C27") (pin "2") (pinfunction "2_2") (pintype "passive"))
      (node (ref "C29") (pin "2") (pinfunction "2_2") (pintype "passive"))
      (node (ref "C3") (pin "2") (pinfunction "2_2") (pintype "passive"))
      (node (ref "C30") (pin "2") (pinfunction "2_2") (pintype "passive"))
      (node (ref "C31") (pin "2") (pinfunction "2_2") (pintype "passive"))
      (node (ref "C32") (pin "2") (pinfunction "2_2") (pintype "passive"))
      (node (ref "C33") (pin "2") (pinfunction "2_2") (pintype "passive"))
      (node (ref "C34") (pin "2") (pinfunction "2_2") (pintype "passive"))
      (node (ref "C37") (pin "2") (pinfunction "2_2") (pintype "passive"))
      (node (ref "C38") (pin "2") (pinfunction "2_2") (pintype "passive"))
      (node (ref "C39") (pin "2") (pinfunction "2_2") (pintype "passive"))
      (node (ref "C4") (pin "2") (pinfunction "2_2") (pintype "passive"))
      (node (ref "C42") (pin "2") (pinfunction "2_2") (pintype "passive"))
      (node (ref "C43") (pin "2") (pinfunction "2_2") (pintype "passive"))
      (node (ref "C5") (pin "2") (pinfunction "2_2") (pintype "passive"))
      (node (ref "C6") (pin "2") (pinfunction "2_2") (pintype "passive"))
      (node (ref "C7") (pin "2") (pinfunction "2_2") (pintype "passive"))
      (node (ref "C8") (pin "2") (pinfunction "2_2") (pintype "passive"))
      (node (ref "C9") (pin "2") (pinfunction "2_2") (pintype "passive"))
      (node (ref "D3") (pin "2") (pinfunction "GND_2") (pintype "bidirectional"))
      (node (ref "D4") (pin "1") (pinfunction "K_1") (pintype "bidirectional"))
      (node (ref "EPD_C1") (pin "1") (pinfunction "1_1") (pintype "passive"))
      (node (ref "EPD_C10") (pin "1") (pinfunction "1_1") (pintype "passive"))
      (node (ref "EPD_C11") (pin "1") (pinfunction "1_1") (pintype "passive"))
      (node (ref "EPD_C12") (pin "1") (pinfunction "1_1") (pintype "passive"))
      (node (ref "EPD_C2") (pin "1") (pinfunction "1_1") (pintype "passive"))
      (node (ref "EPD_C5") (pin "1") (pinfunction "1_1") (pintype "passive"))
      (node (ref "EPD_C6") (pin "1") (pinfunction "1_1") (pintype "passive"))
      (node (ref "EPD_C7") (pin "1") (pinfunction "1_1") (pintype "passive"))
      (node (ref "EPD_C8") (pin "1") (pinfunction "1_1") (pintype "passive"))
      (node (ref "EPD_C9") (pin "1") (pinfunction "1_1") (pintype "passive"))
      (node (ref "IC1") (pin "D2") (pinfunction "GND_D2") (pintype "bidirectional"))
      (node (ref "IC2") (pin "B1") (pinfunction "IN/TRIG_B1") (pintype "bidirectional"))
      (node (ref "IC2") (pin "B3") (pinfunction "GND_B3") (pintype "bidirectional"))
      (node (ref "IC3") (pin "8") (pinfunction "GNDIO_8") (pintype "bidirectional"))
      (node (ref "IC3") (pin "9") (pinfunction "GND_9") (pintype "bidirectional"))
      (node (ref "IC9") (pin "B1") (pinfunction "VSEL_B1") (pintype "bidirectional"))
      (node (ref "IC9") (pin "C1") (pinfunction "AGND_C1") (pintype "bidirectional"))
      (node (ref "IC9") (pin "C2") (pinfunction "PGND_1_C2") (pintype "bidirectional"))
      (node (ref "IC9") (pin "C3") (pinfunction "PGND_2_C3") (pintype "bidirectional"))
      (node (ref "J1") (pin "17") (pinfunction "17_17") (pintype "bidirectional"))
      (node (ref "J1") (pin "8") (pinfunction "8_8") (pintype "bidirectional"))
      (node (ref "J1") (pin "MP1") (pinfunction "MP1_MP1") (pintype "bidirectional"))
      (node (ref "J1") (pin "MP2") (pinfunction "MP2_MP2") (pintype "bidirectional"))
      (node (ref "J2") (pin "3") (pinfunction "3_3") (pintype "bidirectional"))
      (node (ref "J2") (pin "5") (pinfunction "5_5") (pintype "bidirectional"))
      (node (ref "J4") (pin "A12_B1") (pinfunction "GND_A12_B1") (pintype "power_in"))
      (node (ref "J4") (pin "A1_B12") (pinfunction "GND_A1_B12") (pintype "power_in"))
      (node (ref "J4") (pin "SH1") (pinfunction "SHIELD_SH1") (pintype "passive"))
      (node (ref "J4") (pin "SH2") (pinfunction "SHIELD_SH2") (pintype "passive"))
      (node (ref "J4") (pin "SH3") (pinfunction "SHIELD_SH3") (pintype "passive"))
      (node (ref "J4") (pin "SH4") (pinfunction "SHIELD_SH4") (pintype "passive"))
      (node (ref "R1_USB") (pin "1") (pinfunction "1_1") (pintype "bidirectional"))
      (node (ref "R2-USB1") (pin "2") (pinfunction "2_2") (pintype "bidirectional"))
      (node (ref "R2_EP_DR") (pin "1") (pinfunction "1_1") (pintype "bidirectional"))
      (node (ref "R3") (pin "1") (pinfunction "1_1") (pintype "bidirectional"))
      (node (ref "R9") (pin "1") (pinfunction "1_1") (pintype "bidirectional"))
      (node (ref "R_TYPE_SEL") (pin "1") (pinfunction "1_1") (pintype "bidirectional"))
      (node (ref "SJ1") (pin "1") (pinfunction "1_1") (pintype "passive"))
      (node (ref "SW_DN") (pin "1") (pinfunction "1_1") (pintype "passive"))
      (node (ref "SW_ENT") (pin "1") (pinfunction "1_1") (pintype "passive"))
      (node (ref "SW_UP") (pin "1") (pinfunction "1_1") (pintype "passive"))
      (node (ref "TP_BAT_GND1") (pin "TP") (pinfunction "TP_TP") (pintype "input"))
      (node (ref "TP_GND") (pin "TP") (pinfunction "TP_TP") (pintype "input"))
      (node (ref "U1") (pin "P$74") (pinfunction "VSS_PAD_P$74") (pintype "bidirectional"))
      (node (ref "U1") (pin "P$75") (pinfunction "VSS_PAD_P$75") (pintype "bidirectional"))
      (node (ref "U1") (pin "P$76") (pinfunction "VSS_PAD_P$76") (pintype "bidirectional"))
      (node (ref "U1") (pin "P$77") (pinfunction "VSS_PAD_P$77") (pintype "bidirectional"))
      (node (ref "U1") (pin "P$78") (pinfunction "VSS_PAD_P$78") (pintype "bidirectional"))
      (node (ref "U1") (pin "P$79") (pinfunction "VSS_PAD_P$79") (pintype "bidirectional"))
      (node (ref "U1") (pin "P$80") (pinfunction "VSS_PAD_P$80") (pintype "bidirectional"))
      (node (ref "U1") (pin "P$81") (pinfunction "VSS_PAD_P$81") (pintype "bidirectional"))
      (node (ref "U1") (pin "P$82") (pinfunction "VSS_PAD_P$82") (pintype "bidirectional"))
      (node (ref "U1") (pin "P$83") (pinfunction "VSS_PAD_P$83") (pintype "bidirectional"))
      (node (ref "U1") (pin "P$84") (pinfunction "VSS_PAD_P$84") (pintype "bidirectional"))
      (node (ref "U1") (pin "P$85") (pinfunction "VSS_PAD_P$85") (pintype "bidirectional"))
      (node (ref "U1") (pin "P$86") (pinfunction "VSS_PAD_P$86") (pintype "bidirectional"))
      (node (ref "U1") (pin "P$87") (pinfunction "VSS_PAD_P$87") (pintype "bidirectional"))
      (node (ref "U1") (pin "P$88") (pinfunction "VSS_PAD_P$88") (pintype "bidirectional"))
      (node (ref "U1") (pin "P$89") (pinfunction "VSS_PAD_P$89") (pintype "bidirectional"))
      (node (ref "U1") (pin "P$90") (pinfunction "VSS_PAD_P$90") (pintype "bidirectional"))
      (node (ref "U1") (pin "P$B7") (pinfunction "VSS_P$B7") (pintype "power_in"))
      (node (ref "U1") (pin "P$F23") (pinfunction "VSS_PA_P$F23") (pintype "bidirectional"))
      (node (ref "U3") (pin "1") (pinfunction "CTG_1") (pintype "power_in"))
      (node (ref "U3") (pin "4") (pinfunction "GND_4") (pintype "power_in"))
      (node (ref "U3") (pin "6") (pinfunction "QSTRT_6") (pintype "input"))
      (node (ref "U3") (pin "9") (pinfunction "EP_9") (pintype "power_in"))
      (node (ref "X1") (pin "2") (pinfunction "2_2") (pintype "passive"))
      (node (ref "X1") (pin "4") (pinfunction "4_4") (pintype "passive"))
    )
    (net (code "15") (name "HAPTIC_EN") (class "Default")
      (node (ref "U1") (pin "P$U1") (pinfunction "P0.12_P$U1") (pintype "bidirectional"))
    )
    (net (code "16") (name "HAPTIC_EN{slash}1.4C") (class "Default")
      (node (ref "IC2") (pin "A1") (pinfunction "EN_A1") (pintype "bidirectional"))
    )
    (net (code "17") (name "IMU_INT1") (class "Default")
      (node (ref "IC3") (pin "5") (pinfunction "INT1_5") (pintype "bidirectional"))
      (node (ref "U1") (pin "P$N1") (pinfunction "P0.08_P$N1") (pintype "bidirectional"))
    )
    (net (code "18") (name "IMU_INT2") (class "Default")
      (node (ref "IC3") (pin "6") (pinfunction "INT2_6") (pintype "bidirectional"))
      (node (ref "U1") (pin "P$P2") (pinfunction "P1.08_P$P2") (pintype "bidirectional"))
    )
    (net (code "19") (name "LX1") (class "Default")
      (node (ref "IC9") (pin "B2") (pinfunction "SW1_1_B2") (pintype "bidirectional"))
      (node (ref "IC9") (pin "B3") (pinfunction "SW1_2_B3") (pintype "bidirectional"))
      (node (ref "L7") (pin "1") (pinfunction "1_1") (pintype "bidirectional"))
    )
    (net (code "20") (name "LX2") (class "Default")
      (node (ref "IC9") (pin "D2") (pinfunction "SW2_1_D2") (pintype "bidirectional"))
      (node (ref "IC9") (pin "D3") (pinfunction "SW2_2_D3") (pintype "bidirectional"))
      (node (ref "L7") (pin "2") (pinfunction "2_2") (pintype "bidirectional"))
    )
    (net (code "21") (name "MOSI") (class "Default")
      (node (ref "J1") (pin "14") (pinfunction "14_14") (pintype "bidirectional"))
      (node (ref "U1") (pin "P$B13") (pinfunction "P0.03/AIN1_P$B13") (pintype "bidirectional"))
    )
    (net (code "22") (name "N$22") (class "Default")
      (node (ref "R17") (pin "1") (pinfunction "1_1") (pintype "bidirectional"))
      (node (ref "R18") (pin "1") (pinfunction "1_1") (pintype "bidirectional"))
    )
    (net (code "23") (name "Net-(ANT1-FEED)") (class "Default")
      (node (ref "ANT1") (pin "1") (pinfunction "FEED_1") (pintype "input"))
      (node (ref "C22") (pin "1") (pinfunction "1_1") (pintype "passive"))
      (node (ref "C4") (pin "1") (pinfunction "1_1") (pintype "passive"))
      (node (ref "L1") (pin "2") (pinfunction "2_2") (pintype "bidirectional"))
    )
    (net (code "24") (name "Net-(D2-K)") (class "Default")
      (node (ref "C2-EP-DR") (pin "1") (pinfunction "1_1") (pintype "passive"))
      (node (ref "D2") (pin "1") (pinfunction "K_1") (pintype "bidirectional"))
      (node (ref "D4") (pin "2") (pinfunction "A_2") (pintype "bidirectional"))
    )
    (net (code "25") (name "Net-(D5-A)") (class "Default")
      (node (ref "C2-EP-DR") (pin "2") (pinfunction "2_2") (pintype "passive"))
      (node (ref "D5") (pin "2") (pinfunction "A_2") (pintype "bidirectional"))
      (node (ref "L5") (pin "1") (pinfunction "1_1") (pintype "passive"))
      (node (ref "Q3") (pin "3") (pinfunction "D_3") (pintype "bidirectional"))
    )
    (net (code "26") (name "Net-(EPD_C1-Pad2)") (class "Default")
      (node (ref "EPD_C1") (pin "2") (pinfunction "2_2") (pintype "passive"))
      (node (ref "J1") (pin "4") (pinfunction "4_4") (pintype "bidirectional"))
    )
    (net (code "27") (name "Net-(EPD_C2-Pad2)") (class "Default")
      (node (ref "EPD_C2") (pin "2") (pinfunction "2_2") (pintype "passive"))
      (node (ref "J1") (pin "3") (pinfunction "3_3") (pintype "bidirectional"))
    )
    (net (code "28") (name "Net-(EPD_C6-Pad2)") (class "Default")
      (node (ref "EPD_C6") (pin "2") (pinfunction "2_2") (pintype "passive"))
      (node (ref "J1") (pin "18") (pinfunction "18_18") (pintype "bidirectional"))
    )
    (net (code "29") (name "Net-(EPD_C7-Pad2)") (class "Default")
      (node (ref "EPD_C7") (pin "2") (pinfunction "2_2") (pintype "passive"))
      (node (ref "J1") (pin "19") (pinfunction "19_19") (pintype "bidirectional"))
    )
    (net (code "30") (name "Net-(EPD_C8-Pad2)") (class "Default")
      (node (ref "EPD_C8") (pin "2") (pinfunction "2_2") (pintype "passive"))
      (node (ref "J1") (pin "20") (pinfunction "20_20") (pintype "bidirectional"))
    )
    (net (code "31") (name "Net-(EPD_C10-Pad2)") (class "Default")
      (node (ref "EPD_C10") (pin "2") (pinfunction "2_2") (pintype "passive"))
      (node (ref "J1") (pin "22") (pinfunction "22_22") (pintype "bidirectional"))
    )
    (net (code "32") (name "Net-(EPD_C12-Pad2)") (class "Default")
      (node (ref "EPD_C12") (pin "2") (pinfunction "2_2") (pintype "passive"))
      (node (ref "J1") (pin "24") (pinfunction "24_24") (pintype "bidirectional"))
    )
    (net (code "33") (name "Net-(IC1-TS{slash}MR)") (class "Default")
      (node (ref "IC1") (pin "D1") (pinfunction "TS/MR_D1") (pintype "bidirectional"))
      (node (ref "R9") (pin "2") (pinfunction "2_2") (pintype "bidirectional"))
    )
    (net (code "34") (name "Net-(IC2-REG)") (class "Default")
      (node (ref "C32") (pin "1") (pinfunction "1_1") (pintype "passive"))
      (node (ref "IC2") (pin "A2") (pinfunction "REG_A2") (pintype "bidirectional"))
    )
    (net (code "35") (name "Net-(IC3-SDO)") (class "Default")
      (node (ref "IC3") (pin "1") (pinfunction "SDO_1") (pintype "bidirectional"))
      (node (ref "R3") (pin "2") (pinfunction "2_2") (pintype "bidirectional"))
    )
    (net (code "36") (name "Net-(IC9-SCL)") (class "Default")
      (node (ref "IC9") (pin "D1") (pinfunction "SCL_D1") (pintype "bidirectional"))
      (node (ref "R4") (pin "2") (pinfunction "2_2") (pintype "bidirectional"))
    )
    (net (code "37") (name "Net-(IC9-SDA)") (class "Default")
      (node (ref "IC9") (pin "E1") (pinfunction "SDA_E1") (pintype "bidirectional"))
      (node (ref "R2") (pin "2") (pinfunction "2_2") (pintype "bidirectional"))
    )
    (net (code "38") (name "Net-(J4-CC1)") (class "Default")
      (node (ref "J4") (pin "A5") (pinfunction "CC1_A5") (pintype "bidirectional"))
      (node (ref "R1_USB") (pin "2") (pinfunction "2_2") (pintype "bidirectional"))
    )
    (net (code "39") (name "Net-(J4-CC2)") (class "Default")
      (node (ref "J4") (pin "B5") (pinfunction "CC2_B5") (pintype "bidirectional"))
      (node (ref "R2-USB1") (pin "1") (pinfunction "1_1") (pintype "bidirectional"))
    )
    (net (code "40") (name "Net-(L2-Pad2)") (class "Default")
      (node (ref "L2") (pin "2") (pinfunction "2_2") (pintype "passive"))
      (node (ref "L3") (pin "1") (pinfunction "1_1") (pintype "passive"))
    )
    (net (code "41") (name "Net-(R1_EP_DR-Pad1)") (class "Default")
      (node (ref "R1_EP_DR") (pin "1") (pinfunction "1_1") (pintype "bidirectional"))
      (node (ref "R_TYPE_SEL") (pin "2") (pinfunction "2_2") (pintype "bidirectional"))
      (node (ref "SJ1") (pin "2") (pinfunction "2_2") (pintype "passive"))
    )
    (net (code "42") (name "Net-(U1-ANT)") (class "Default")
      (node (ref "C3") (pin "1") (pinfunction "1_1") (pintype "passive"))
      (node (ref "L1") (pin "1") (pinfunction "1_1") (pintype "bidirectional"))
      (node (ref "U1") (pin "P$H23") (pinfunction "ANT_P$H23") (pintype "bidirectional"))
    )
    (net (code "43") (name "Net-(U1-DCC)") (class "Default")
      (node (ref "L2") (pin "1") (pinfunction "1_1") (pintype "passive"))
      (node (ref "U1") (pin "P$B3") (pinfunction "DCC_P$B3") (pintype "output"))
    )
    (net (code "44") (name "Net-(U1-DEC1)") (class "Default")
      (node (ref "C5") (pin "1") (pinfunction "1_1") (pintype "passive"))
      (node (ref "U1") (pin "P$C1") (pinfunction "DEC1_P$C1") (pintype "power_in"))
    )
    (net (code "45") (name "Net-(U1-DEC2)") (class "Default")
      (node (ref "C13") (pin "1") (pinfunction "1_1") (pintype "passive"))
      (node (ref "U1") (pin "P$A18") (pinfunction "DEC2_P$A18") (pintype "bidirectional"))
    )
    (net (code "46") (name "Net-(U1-DEC3)") (class "Default")
      (node (ref "C11") (pin "1") (pinfunction "1_1") (pintype "passive"))
      (node (ref "U1") (pin "P$D23") (pinfunction "DEC3_P$D23") (pintype "bidirectional"))
    )
    (net (code "47") (name "Net-(U1-DEC3V3)") (class "Default")
      (node (ref "C20") (pin "1") (pinfunction "1_1") (pintype "passive"))
      (node (ref "U1") (pin "P$AC5") (pinfunction "DEC3V3_P$AC5") (pintype "bidirectional"))
    )
    (net (code "48") (name "Net-(U1-DEC4)") (class "Default")
      (node (ref "C10") (pin "1") (pinfunction "1_1") (pintype "passive"))
      (node (ref "C15") (pin "1") (pinfunction "1_1") (pintype "passive"))
      (node (ref "C16") (pin "1") (pinfunction "1_1") (pintype "passive"))
      (node (ref "L3") (pin "2") (pinfunction "2_2") (pintype "passive"))
      (node (ref "U1") (pin "P$B5") (pinfunction "DEC4_P$B5") (pintype "power_in"))
      (node (ref "U1") (pin "P$E24") (pinfunction "DEC6_P$E24") (pintype "bidirectional"))
    )
    (net (code "49") (name "Net-(U1-DEC5)") (class "Default")
      (node (ref "C9") (pin "1") (pinfunction "1_1") (pintype "passive"))
      (node (ref "U1") (pin "P$N24") (pinfunction "DEC5_P$N24") (pintype "bidirectional"))
    )
    (net (code "50") (name "Net-(U1-P0.00{slash}XL1)") (class "Default")
      (node (ref "C17") (pin "2") (pinfunction "2_2") (pintype "passive"))
      (node (ref "U1") (pin "P$D2") (pinfunction "P0.00/XL1_P$D2") (pintype "bidirectional"))
      (node (ref "X2") (pin "2") (pinfunction "2_2") (pintype "passive"))
    )
    (net (code "51") (name "Net-(U1-P0.01{slash}XL2)") (class "Default")
      (node (ref "C18") (pin "2") (pinfunction "2_2") (pintype "passive"))
      (node (ref "U1") (pin "P$F2") (pinfunction "P0.01/XL2_P$F2") (pintype "bidirectional"))
      (node (ref "X2") (pin "1") (pinfunction "1_1") (pintype "passive"))
    )
    (net (code "52") (name "Net-(U1-XC1)") (class "Default")
      (node (ref "C1") (pin "1") (pinfunction "1_1") (pintype "passive"))
      (node (ref "U1") (pin "P$B24") (pinfunction "XC1_P$B24") (pintype "input"))
      (node (ref "X1") (pin "1") (pinfunction "1_1") (pintype "passive"))
    )
    (net (code "53") (name "Net-(U1-XC2)") (class "Default")
      (node (ref "C2") (pin "1") (pinfunction "1_1") (pintype "passive"))
      (node (ref "U1") (pin "P$A23") (pinfunction "XC2_P$A23") (pintype "output"))
      (node (ref "X1") (pin "3") (pinfunction "3_3") (pintype "passive"))
    )
    (net (code "54") (name "OUT+") (class "Default")
      (node (ref "IC2") (pin "A3") (pinfunction "OUT+_A3") (pintype "bidirectional"))
      (node (ref "TP_OP") (pin "TP") (pinfunction "TP_TP") (pintype "input"))
    )
    (net (code "55") (name "OUT-") (class "Default")
      (node (ref "IC2") (pin "C3") (pinfunction "OUT-_C3") (pintype "bidirectional"))
      (node (ref "TP_ON") (pin "TP") (pinfunction "TP_TP") (pintype "input"))
    )
    (net (code "56") (name "P0.04") (class "Default")
      (node (ref "U1") (pin "P$J1") (pinfunction "P0.04/AIN2_P$J1") (pintype "bidirectional"))
    )
    (net (code "57") (name "P0.09") (class "Default")
      (node (ref "U1") (pin "P$L24") (pinfunction "P0.09/NFC1_P$L24") (pintype "bidirectional"))
    )
    (net (code "58") (name "P0.13") (class "Default")
      (node (ref "C29") (pin "1") (pinfunction "1_1") (pintype "passive"))
      (node (ref "C30") (pin "1") (pinfunction "1_1") (pintype "passive"))
      (node (ref "C31") (pin "1") (pinfunction "1_1") (pintype "passive"))
      (node (ref "R5") (pin "1") (pinfunction "1_1") (pintype "bidirectional"))
      (node (ref "R7") (pin "1") (pinfunction "1_1") (pintype "bidirectional"))
      (node (ref "R8") (pin "1") (pinfunction "1_1") (pintype "bidirectional"))
      (node (ref "SW_DN") (pin "2") (pinfunction "2_2") (pintype "passive"))
      (node (ref "SW_ENT") (pin "2") (pinfunction "2_2") (pintype "passive"))
      (node (ref "SW_UP") (pin "2") (pinfunction "2_2") (pintype "passive"))
      (node (ref "U1") (pin "P$AD8") (pinfunction "P0.13_P$AD8") (pintype "bidirectional"))
    )
    (net (code "59") (name "P0.14") (class "Default")
      (node (ref "U1") (pin "P$AC9") (pinfunction "P0.14_P$AC9") (pintype "bidirectional"))
    )
    (net (code "60") (name "P0.19") (class "Default")
      (node (ref "U1") (pin "P$AC15") (pinfunction "P0.19_P$AC15") (pintype "bidirectional"))
    )
    (net (code "61") (name "P0.20") (class "Default")
      (node (ref "U1") (pin "P$AD16") (pinfunction "P0.20_P$AD16") (pintype "bidirectional"))
    )
    (net (code "62") (name "P0.21") (class "Default")
      (node (ref "U1") (pin "P$AC17") (pinfunction "P0.21_P$AC17") (pintype "bidirectional"))
    )
    (net (code "63") (name "P0.22") (class "Default")
      (node (ref "U1") (pin "P$AD18") (pinfunction "P0.22_P$AD18") (pintype "bidirectional"))
    )
    (net (code "64") (name "P0.23") (class "Default")
      (node (ref "U1") (pin "P$AC19") (pinfunction "P0.23_P$AC19") (pintype "bidirectional"))
    )
    (net (code "65") (name "P0.24") (class "Default")
      (node (ref "U1") (pin "P$AD20") (pinfunction "P0.24_P$AD20") (pintype "bidirectional"))
    )
    (net (code "66") (name "P0.25") (class "Default")
      (node (ref "U1") (pin "P$AC21") (pinfunction "P0.25_P$AC21") (pintype "bidirectional"))
    )
    (net (code "67") (name "P0.26") (class "Default")
      (node (ref "U1") (pin "P$G1") (pinfunction "P0.26_P$G1") (pintype "bidirectional"))
    )
    (net (code "68") (name "P0.27") (class "Default")
      (node (ref "U1") (pin "P$H2") (pinfunction "P0.27_P$H2") (pintype "bidirectional"))
    )
    (net (code "69") (name "P0.28") (class "Default")
      (node (ref "U1") (pin "P$B11") (pinfunction "P0.28/AIN4_P$B11") (pintype "bidirectional"))
    )
    (net (code "70") (name "P0.29") (class "Default")
      (node (ref "U1") (pin "P$A10") (pinfunction "P0.29/AIN5_P$A10") (pintype "bidirectional"))
    )
    (net (code "71") (name "P0.30") (class "Default")
      (node (ref "U1") (pin "P$B9") (pinfunction "P0.30/AIN6_P$B9") (pintype "bidirectional"))
    )
    (net (code "72") (name "P0.31") (class "Default")
      (node (ref "U1") (pin "P$A8") (pinfunction "P0.31/AIN7_P$A8") (pintype "bidirectional"))
    )
    (net (code "73") (name "P1.01") (class "Default")
      (node (ref "Q1") (pin "1") (pinfunction "G_1") (pintype "bidirectional"))
      (node (ref "R_PWR_EPD") (pin "1") (pinfunction "1_1") (pintype "bidirectional"))
      (node (ref "U1") (pin "P$Y23") (pinfunction "P1.01_P$Y23") (pintype "bidirectional"))
    )
    (net (code "74") (name "P1.02") (class "Default")
      (node (ref "U1") (pin "P$W24") (pinfunction "P1.02_P$W24") (pintype "bidirectional"))
    )
    (net (code "75") (name "P1.03") (class "Default")
      (node (ref "U1") (pin "P$V23") (pinfunction "P1.03_P$V23") (pintype "bidirectional"))
    )
    (net (code "76") (name "P1.04") (class "Default")
      (node (ref "U1") (pin "P$U24") (pinfunction "P1.04_P$U24") (pintype "bidirectional"))
    )
    (net (code "77") (name "P1.05") (class "Default")
      (node (ref "U1") (pin "P$T23") (pinfunction "P1.05_P$T23") (pintype "bidirectional"))
    )
    (net (code "78") (name "P1.06") (class "Default")
      (node (ref "U1") (pin "P$R24") (pinfunction "P1.06_P$R24") (pintype "bidirectional"))
    )
    (net (code "79") (name "P1.07") (class "Default")
      (node (ref "U1") (pin "P$P23") (pinfunction "P1.07_P$P23") (pintype "bidirectional"))
    )
    (net (code "80") (name "P1.09") (class "Default")
      (node (ref "U1") (pin "P$R1") (pinfunction "P1.09_P$R1") (pintype "bidirectional"))
    )
    (net (code "81") (name "P1.10") (class "Default")
      (node (ref "U1") (pin "P$A20") (pinfunction "P1.10_P$A20") (pintype "bidirectional"))
    )
    (net (code "82") (name "P1.11") (class "Default")
      (node (ref "U1") (pin "P$B19") (pinfunction "P1.11_P$B19") (pintype "bidirectional"))
    )
    (net (code "83") (name "P1.12") (class "Default")
      (node (ref "U1") (pin "P$B17") (pinfunction "P1.12_P$B17") (pintype "bidirectional"))
    )
    (net (code "84") (name "P1.13") (class "Default")
      (node (ref "U1") (pin "P$A16") (pinfunction "P1.13_P$A16") (pintype "bidirectional"))
    )
    (net (code "85") (name "P1.14") (class "Default")
      (node (ref "U1") (pin "P$B15") (pinfunction "P1.14_P$B15") (pintype "bidirectional"))
    )
    (net (code "86") (name "P1.15") (class "Default")
      (node (ref "U1") (pin "P$A14") (pinfunction "P1.15_P$A14") (pintype "bidirectional"))
    )
    (net (code "87") (name "PMIC_INT") (class "Default")
      (node (ref "IC1") (pin "A1") (pinfunction "~{INT}_A1") (pintype "bidirectional"))
      (node (ref "U1") (pin "P$T2") (pinfunction "P0.11_P$T2") (pintype "bidirectional"))
    )
    (net (code "88") (name "PREVGH") (class "Default")
      (node (ref "D5") (pin "1") (pinfunction "K_1") (pintype "bidirectional"))
      (node (ref "EPD_C9") (pin "2") (pinfunction "2_2") (pintype "passive"))
      (node (ref "J1") (pin "21") (pinfunction "21_21") (pintype "bidirectional"))
    )
    (net (code "89") (name "PREVGL") (class "Default")
      (node (ref "D2") (pin "2") (pinfunction "A_2") (pintype "bidirectional"))
      (node (ref "EPD_C11") (pin "2") (pinfunction "2_2") (pintype "passive"))
      (node (ref "J1") (pin "23") (pinfunction "23_23") (pintype "bidirectional"))
    )
    (net (code "90") (name "RESE") (class "Default")
      (node (ref "J1") (pin "2") (pinfunction "2_2") (pintype "bidirectional"))
      (node (ref "Q3") (pin "2") (pinfunction "S_2") (pintype "bidirectional"))
      (node (ref "R1_EP_DR") (pin "2") (pinfunction "2_2") (pintype "bidirectional"))
    )
    (net (code "91") (name "RESET") (class "Default")
      (node (ref "J2") (pin "6") (pinfunction "6_6") (pintype "bidirectional"))
      (node (ref "TP_RESET") (pin "TP") (pinfunction "TP_TP") (pintype "input"))
      (node (ref "U1") (pin "P$AC13") (pinfunction "P0.18/RESET_P$AC13") (pintype "bidirectional"))
    )
    (net (code "92") (name "SCK") (class "Default")
      (node (ref "J1") (pin "13") (pinfunction "13_13") (pintype "bidirectional"))
      (node (ref "U1") (pin "P$A12") (pinfunction "P0.02/AIN0_P$A12") (pintype "bidirectional"))
    )
    (net (code "93") (name "SCL") (class "Default")
      (node (ref "IC1") (pin "B1") (pinfunction "SCL_B1") (pintype "bidirectional"))
      (node (ref "IC2") (pin "C1") (pinfunction "SCL_C1") (pintype "bidirectional"))
      (node (ref "IC3") (pin "12") (pinfunction "SCX_12") (pintype "bidirectional"))
      (node (ref "R17") (pin "2") (pinfunction "2_2") (pintype "bidirectional"))
      (node (ref "R4") (pin "1") (pinfunction "1_1") (pintype "bidirectional"))
      (node (ref "TP_SCL") (pin "TP") (pinfunction "TP_TP") (pintype "input"))
      (node (ref "U1") (pin "P$M2") (pinfunction "P0.07_P$M2") (pintype "bidirectional"))
      (node (ref "U3") (pin "7") (pinfunction "SCL_7") (pintype "input"))
    )
    (net (code "94") (name "SDA") (class "Default")
      (node (ref "IC1") (pin "C1") (pinfunction "SDA_C1") (pintype "bidirectional"))
      (node (ref "IC3") (pin "2") (pinfunction "SDX_2") (pintype "bidirectional"))
      (node (ref "R18") (pin "2") (pinfunction "2_2") (pintype "bidirectional"))
      (node (ref "R2") (pin "1") (pinfunction "1_1") (pintype "bidirectional"))
      (node (ref "TP_SDA") (pin "TP") (pinfunction "TP_TP") (pintype "input"))
      (node (ref "U1") (pin "P$L1") (pinfunction "P0.06_P$L1") (pintype "bidirectional"))
      (node (ref "U3") (pin "8") (pinfunction "SDA_8") (pintype "bidirectional"))
    )
    (net (code "95") (name "SDA{slash}1.4C") (class "Default")
      (node (ref "IC2") (pin "B2") (pinfunction "SDA_B2") (pintype "bidirectional"))
    )
    (net (code "96") (name "SWDCLK") (class "Default")
      (node (ref "J2") (pin "4") (pinfunction "4_4") (pintype "bidirectional"))
      (node (ref "TP_SWDCLK") (pin "TP") (pinfunction "TP_TP") (pintype "input"))
      (node (ref "U1") (pin "P$AA24") (pinfunction "SWDCLK_P$AA24") (pintype "input"))
    )
    (net (code "97") (name "SWDIO") (class "Default")
      (node (ref "J2") (pin "2") (pinfunction "2_2") (pintype "bidirectional"))
      (node (ref "TP_SWDIO") (pin "TP") (pinfunction "TP_TP") (pintype "input"))
      (node (ref "U1") (pin "P$AC24") (pinfunction "SWDIO_P$AC24") (pintype "bidirectional"))
    )
    (net (code "98") (name "SWO") (class "Default")
      (node (ref "TP_SWO") (pin "TP") (pinfunction "TP_TP") (pintype "input"))
      (node (ref "U1") (pin "P$AD22") (pinfunction "P1.00_P$AD22") (pintype "bidirectional"))
    )
    (net (code "99") (name "VBAT") (class "Default")
      (node (ref "C27") (pin "1") (pinfunction "1_1") (pintype "passive"))
      (node (ref "C37") (pin "1") (pinfunction "1_1") (pintype "passive"))
      (node (ref "IC1") (pin "C2") (pinfunction "BAT_C2") (pintype "bidirectional"))
      (node (ref "TP_VBAT1") (pin "TP") (pinfunction "TP_TP") (pintype "input"))
      (node (ref "U3") (pin "2") (pinfunction "CELL_2") (pintype "power_in"))
      (node (ref "U3") (pin "3") (pinfunction "VDD_3") (pintype "power_in"))
    )
    (net (code "100") (name "VBUS") (class "Default")
      (node (ref "C21") (pin "1") (pinfunction "1_1") (pintype "passive"))
      (node (ref "C38") (pin "1") (pinfunction "1_1") (pintype "passive"))
      (node (ref "C42") (pin "1") (pinfunction "1_1") (pintype "passive"))
      (node (ref "C43") (pin "1") (pinfunction "1_1") (pintype "passive"))
      (node (ref "D3") (pin "5") (pinfunction "VBUS_5") (pintype "bidirectional"))
      (node (ref "IC1") (pin "A2") (pinfunction "IN_A2") (pintype "bidirectional"))
      (node (ref "J4") (pin "A4_B9") (pinfunction "VBUS_A4_B9") (pintype "power_in"))
      (node (ref "J4") (pin "A9_B4") (pinfunction "VBUS_A9_B4") (pintype "power_in"))
      (node (ref "U1") (pin "P$AD2") (pinfunction "VBUS_P$AD2") (pintype "power_in"))
    )
    (net (code "101") (name "VREG") (class "Default")
      (node (ref "C23") (pin "2") (pinfunction "2_2") (pintype "passive"))
      (node (ref "C24") (pin "2") (pinfunction "2_2") (pintype "passive"))
      (node (ref "C39") (pin "1") (pinfunction "1_1") (pintype "passive"))
      (node (ref "IC1") (pin "B2") (pinfunction "SYS_B2") (pintype "bidirectional"))
      (node (ref "IC9") (pin "A1") (pinfunction "EN_A1") (pintype "bidirectional"))
      (node (ref "IC9") (pin "A2") (pinfunction "VIN_1_A2") (pintype "bidirectional"))
      (node (ref "IC9") (pin "A3") (pinfunction "VIN_2_A3") (pintype "bidirectional"))
      (node (ref "TP_VREG") (pin "TP") (pinfunction "TP_TP") (pintype "input"))
    )
    (net (code "102") (name "unconnected-(ANT1-NC-Pad2)") (class "Default")
      (node (ref "ANT1") (pin "2") (pinfunction "NC_2") (pintype "no_connect"))
    )
    (net (code "103") (name "unconnected-(IC3-ASCL-Pad11)") (class "Default")
      (node (ref "IC3") (pin "11") (pinfunction "ASCL_11") (pintype "bidirectional"))
    )
    (net (code "104") (name "unconnected-(IC3-ASDA-Pad4)") (class "Default")
      (node (ref "IC3") (pin "4") (pinfunction "ASDA_4") (pintype "bidirectional"))
    )
    (net (code "105") (name "unconnected-(J1-Pad5)") (class "Default")
      (node (ref "J1") (pin "5") (pinfunction "5_5") (pintype "bidirectional"))
    )
    (net (code "106") (name "unconnected-(J1-Pad6)") (class "Default")
      (node (ref "J1") (pin "6") (pinfunction "6_6") (pintype "bidirectional"))
    )
    (net (code "107") (name "unconnected-(J1-Pad7)") (class "Default")
      (node (ref "J1") (pin "7") (pinfunction "7_7") (pintype "bidirectional"))
    )
    (net (code "108") (name "unconnected-(J4-SBU1-PadA8)") (class "Default")
      (node (ref "J4") (pin "A8") (pinfunction "SBU1_A8") (pintype "bidirectional"))
    )
    (net (code "109") (name "unconnected-(J4-SBU2-PadB8)") (class "Default")
      (node (ref "J4") (pin "B8") (pinfunction "SBU2_B8") (pintype "bidirectional"))
    )
    (net (code "110") (name "unconnected-(U1-DCCH-PadP$AB2)") (class "Default")
      (node (ref "U1") (pin "P$AB2") (pinfunction "DCCH_P$AB2") (pintype "bidirectional"))
    )
  )
)
